# Main_Schematic.net
KiCad netlist of a schematic drawn in Altium Designer
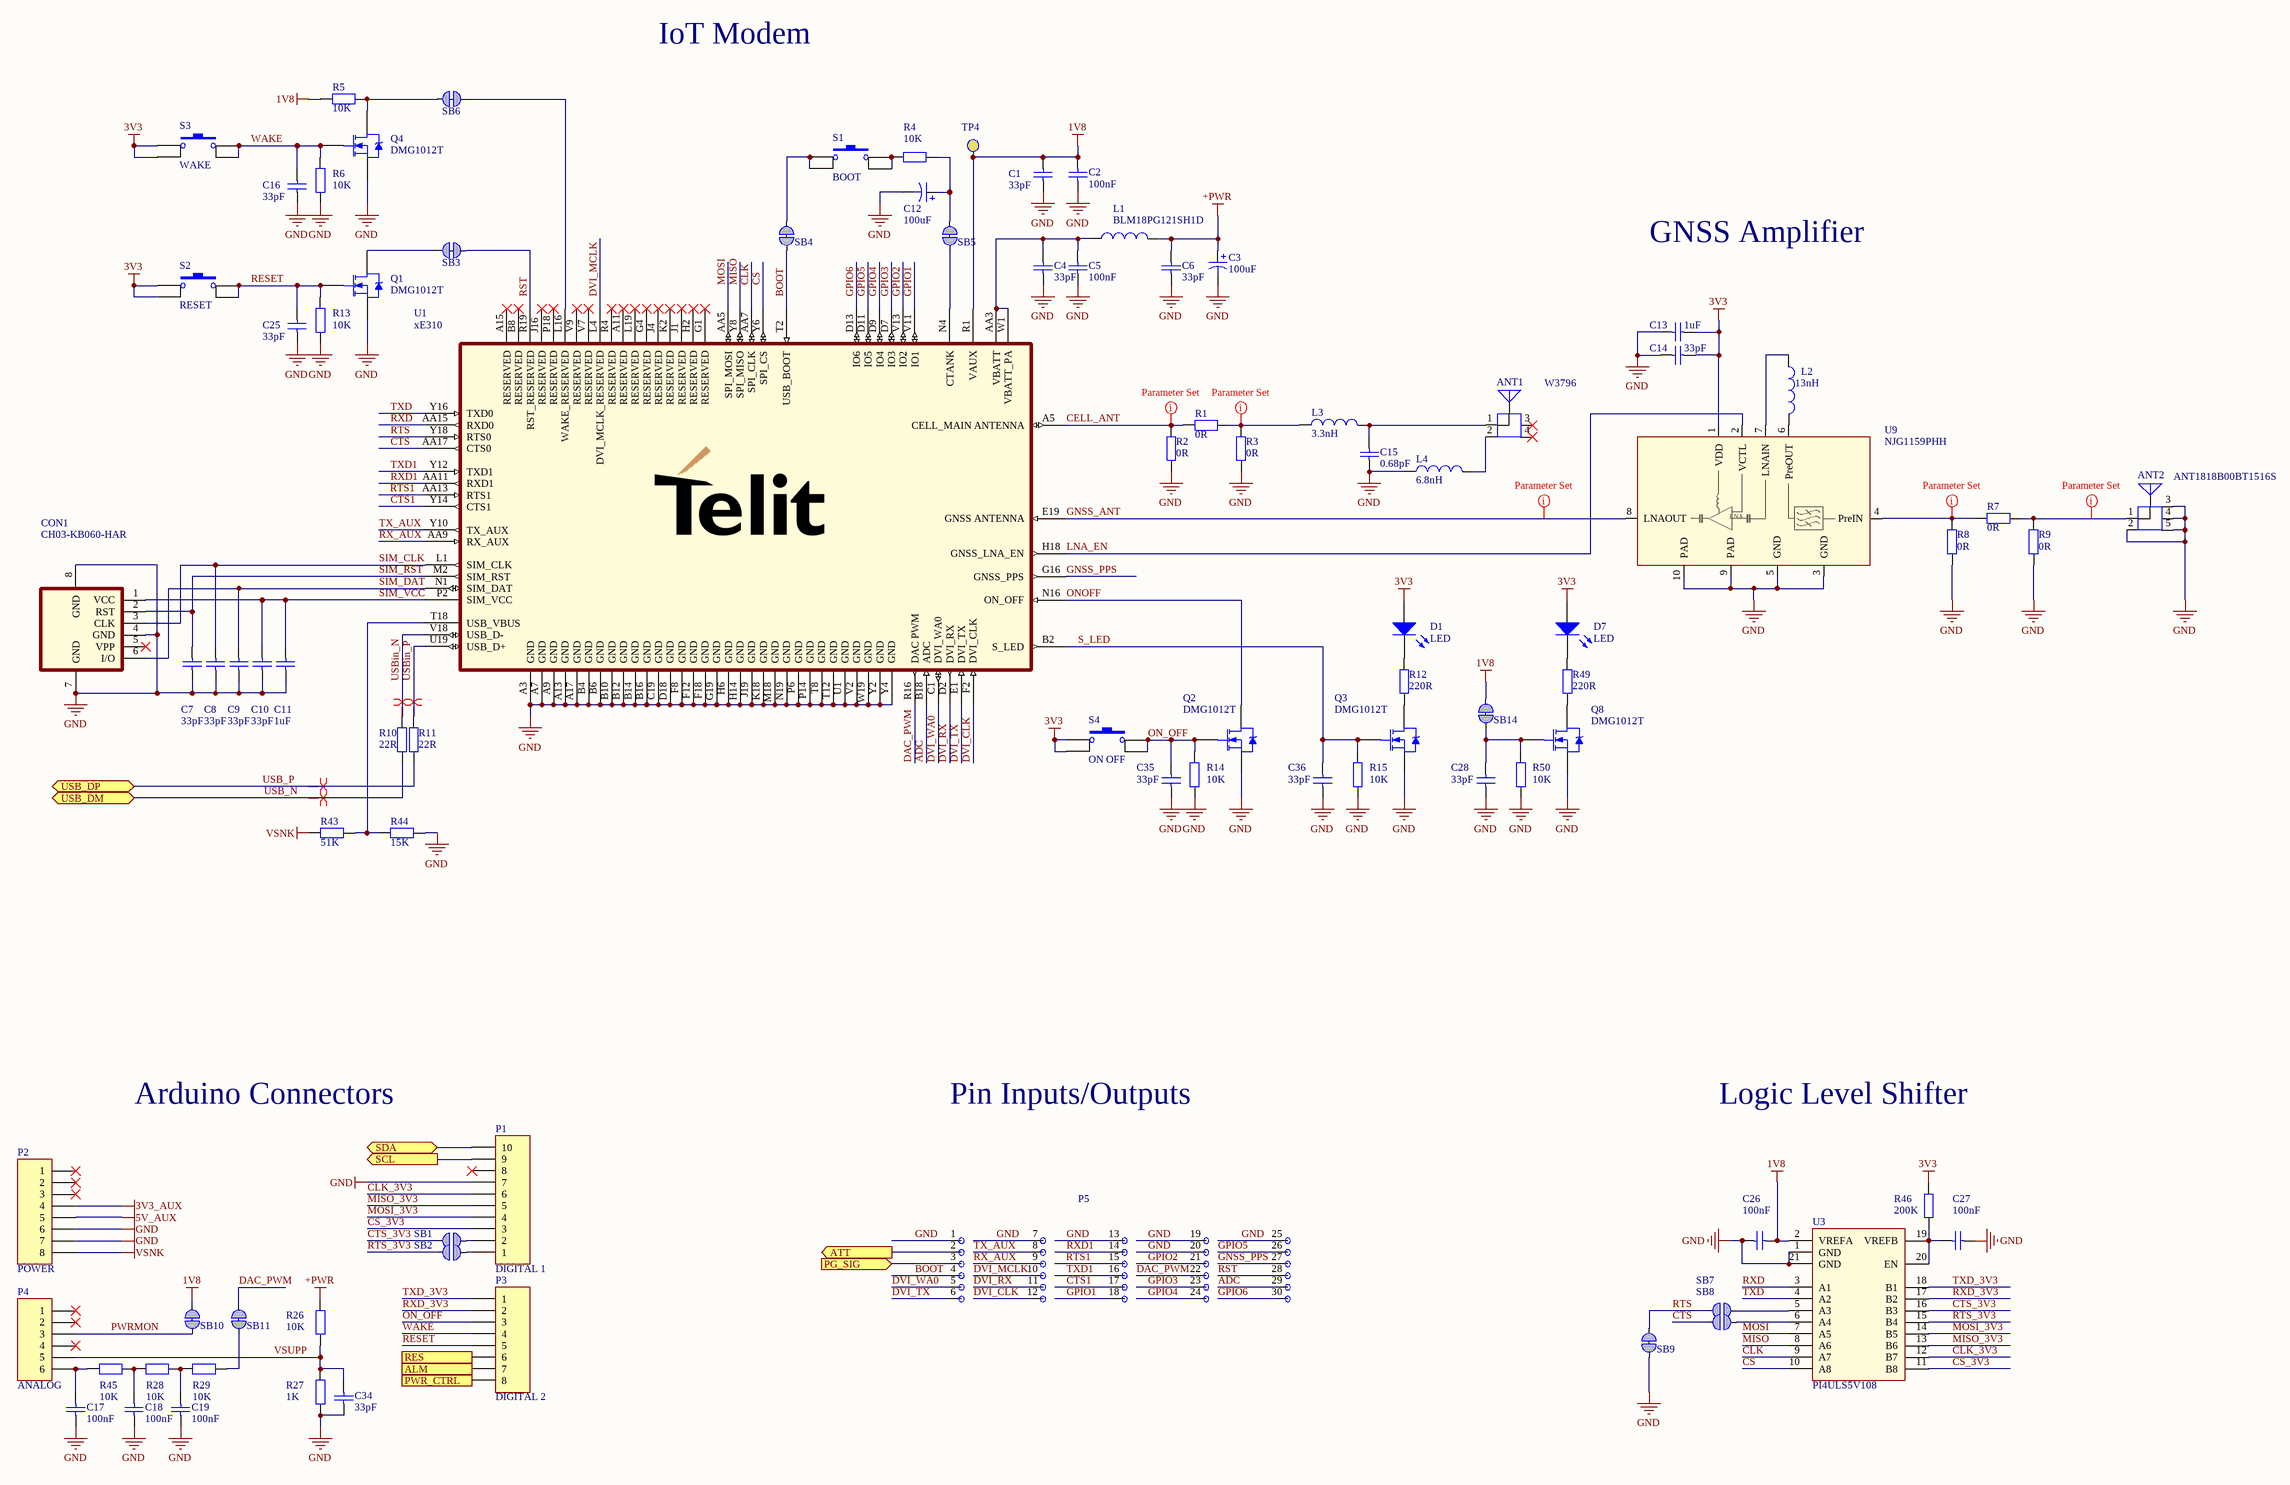
[diagram p0: Main_Schematic.SchDoc]

(export (version "E")
  (design (tool "Eeschema 10.0.6"))
  (components
    (comp (ref "ANT1")
      (value "W3796")
      (footprint "W3796")
      (description "Generic Antenna")
      (fields (field (name "MANUFACTURER") "Pulse"))
      (libsource (lib "RUT_GE310_GNSS") (part "Antenna"))
    )
    (comp (ref "ANT2")
      (value "ANT1818B00BT1516S")
      (footprint "ANT1818B00BT1516S")
      (description "Generic Antenna")
      (fields (field (name "MANUFACTURER") "Yegeo"))
      (libsource (lib "") (part "Antenna_1"))
    )
    (comp (ref "C1")
      (value "33pF")
      (footprint "C0402")
      (description "Capacitor (Semiconductor SIM Model)")
      (fields (field (name "MANUFACTURER") "AVX") (field (name "MANUFACTURER PART NO.") "04025A330JAT2A"))
      (libsource (lib "Miscellaneous Devices") (part "Cap Semi"))
    )
    (comp (ref "C2")
      (value "100nF")
      (footprint "C0402")
      (description "Capacitor (Semiconductor SIM Model)")
      (fields
        (field (name "MANUFACTURER") "YAGEO")
        (field (name "MANUFACTURER PART NO.") "CC0402KRX7R9BB104")
      )
      (libsource (lib "Miscellaneous Devices") (part "Cap Semi"))
    )
    (comp (ref "C3")
      (value "100uF")
      (footprint "Case-B")
      (fields
        (field (name "MANUFACTURER") "AVX")
        (field (name "MANUFACTURER PART NO.") "TPSB107M006R0250")
        (field (name "Comment") "electrolytic capacitor")
      )
      (libsource (lib "Miscellaneous Devices") (part "Cap Pol1"))
    )
    (comp (ref "C4")
      (value "33pF")
      (footprint "C0402")
      (description "Capacitor (Semiconductor SIM Model)")
      (fields (field (name "MANUFACTURER") "AVX") (field (name "MANUFACTURER PART NO.") "04025A330JAT2A"))
      (libsource (lib "Miscellaneous Devices") (part "Cap Semi"))
    )
    (comp (ref "C5")
      (value "100nF")
      (footprint "C0402")
      (description "Capacitor (Semiconductor SIM Model)")
      (fields
        (field (name "MANUFACTURER") "YAGEO")
        (field (name "MANUFACTURER PART NO.") "CC0402KRX7R9BB104")
      )
      (libsource (lib "Miscellaneous Devices") (part "Cap Semi"))
    )
    (comp (ref "C6")
      (value "33pF")
      (footprint "C0402")
      (description "Capacitor (Semiconductor SIM Model)")
      (fields (field (name "MANUFACTURER") "AVX") (field (name "MANUFACTURER PART NO.") "04025A330JAT2A"))
      (libsource (lib "Miscellaneous Devices") (part "Cap Semi"))
    )
    (comp (ref "C7")
      (value "33pF")
      (footprint "C0402")
      (description "Capacitor (Semiconductor SIM Model)")
      (fields (field (name "MANUFACTURER") "AVX") (field (name "MANUFACTURER PART NO.") "04025A330JAT2A"))
      (libsource (lib "Miscellaneous Devices") (part "Cap Semi"))
    )
    (comp (ref "C8")
      (value "33pF")
      (footprint "C0402")
      (description "Capacitor (Semiconductor SIM Model)")
      (fields (field (name "MANUFACTURER") "AVX") (field (name "MANUFACTURER PART NO.") "04025A330JAT2A"))
      (libsource (lib "Miscellaneous Devices") (part "Cap Semi"))
    )
    (comp (ref "C9")
      (value "33pF")
      (footprint "C0402")
      (description "Capacitor (Semiconductor SIM Model)")
      (fields (field (name "MANUFACTURER") "AVX") (field (name "MANUFACTURER PART NO.") "04025A330JAT2A"))
      (libsource (lib "Miscellaneous Devices") (part "Cap Semi"))
    )
    (comp (ref "C10")
      (value "33pF")
      (footprint "C0402")
      (description "Capacitor (Semiconductor SIM Model)")
      (fields (field (name "MANUFACTURER") "AVX") (field (name "MANUFACTURER PART NO.") "04025A330JAT2A"))
      (libsource (lib "Miscellaneous Devices") (part "Cap Semi"))
    )
    (comp (ref "C11")
      (value "1uF")
      (footprint "C0402")
      (description "Capacitor (Semiconductor SIM Model)")
      (fields
        (field (name "MANUFACTURER") "muRata")
        (field (name "MANUFACTURER PART NO.") "GRM155R61E105KA12D")
      )
      (libsource (lib "Miscellaneous Devices") (part "Cap Semi"))
    )
    (comp (ref "C12")
      (value "100uF")
      (footprint "Case-B")
      (fields
        (field (name "MANUFACTURER") "AVX")
        (field (name "MANUFACTURER PART NO.") "TPSB107M006R0250")
        (field (name "Comment") "electrolytic capacitor")
      )
      (libsource (lib "Miscellaneous Devices") (part "Cap Pol1"))
    )
    (comp (ref "C13")
      (value "1uF")
      (footprint "C0402")
      (description "Capacitor (Semiconductor SIM Model)")
      (fields
        (field (name "MANUFACTURER") "muRata")
        (field (name "MANUFACTURER PART NO.") "GRM155R61E105KA12D")
      )
      (libsource (lib "Miscellaneous Devices") (part "Cap Semi"))
    )
    (comp (ref "C14")
      (value "33pF")
      (footprint "C0402")
      (description "Capacitor (Semiconductor SIM Model)")
      (fields (field (name "MANUFACTURER") "AVX") (field (name "MANUFACTURER PART NO.") "04025A330JAT2A"))
      (libsource (lib "Miscellaneous Devices") (part "Cap Semi"))
    )
    (comp (ref "C15")
      (value "0.68pF")
      (footprint "C0402")
      (description "Capacitor (Semiconductor SIM Model)")
      (fields
        (field (name "MANUFACTURER") "YAGEO")
        (field (name "MANUFACTURER PART NO.") "CC0402BRNPO9BNR68")
      )
      (libsource (lib "Miscellaneous Devices") (part "Cap Semi"))
    )
    (comp (ref "C16")
      (value "33pF")
      (footprint "C0402")
      (description "Capacitor (Semiconductor SIM Model)")
      (fields (field (name "MANUFACTURER") "AVX") (field (name "MANUFACTURER PART NO.") "04025A330JAT2A"))
      (libsource (lib "Miscellaneous Devices") (part "Cap Semi"))
    )
    (comp (ref "C17")
      (value "100nF")
      (footprint "C0402")
      (description "Capacitor (Semiconductor SIM Model)")
      (fields
        (field (name "MANUFACTURER") "YAGEO")
        (field (name "MANUFACTURER PART NO.") "CC0402KRX7R9BB104")
      )
      (libsource (lib "Miscellaneous Devices") (part "Cap Semi"))
    )
    (comp (ref "C18")
      (value "100nF")
      (footprint "C0402")
      (description "Capacitor (Semiconductor SIM Model)")
      (fields
        (field (name "MANUFACTURER") "YAGEO")
        (field (name "MANUFACTURER PART NO.") "CC0402KRX7R9BB104")
      )
      (libsource (lib "Miscellaneous Devices") (part "Cap Semi"))
    )
    (comp (ref "C19")
      (value "100nF")
      (footprint "C0402")
      (description "Capacitor (Semiconductor SIM Model)")
      (fields
        (field (name "MANUFACTURER") "YAGEO")
        (field (name "MANUFACTURER PART NO.") "CC0402KRX7R9BB104")
      )
      (libsource (lib "Miscellaneous Devices") (part "Cap Semi"))
    )
    (comp (ref "C25")
      (value "33pF")
      (footprint "C0402")
      (description "Capacitor (Semiconductor SIM Model)")
      (fields (field (name "MANUFACTURER") "AVX") (field (name "MANUFACTURER PART NO.") "04025A330JAT2A"))
      (libsource (lib "Miscellaneous Devices") (part "Cap Semi"))
    )
    (comp (ref "C26")
      (value "100nF")
      (footprint "C0402")
      (description "Capacitor (Semiconductor SIM Model)")
      (fields
        (field (name "MANUFACTURER") "YAGEO")
        (field (name "MANUFACTURER PART NO.") "CC0402KRX7R9BB104")
      )
      (libsource (lib "Miscellaneous Devices") (part "Cap Semi"))
    )
    (comp (ref "C27")
      (value "100nF")
      (footprint "C0402")
      (description "Capacitor (Semiconductor SIM Model)")
      (fields
        (field (name "MANUFACTURER") "YAGEO")
        (field (name "MANUFACTURER PART NO.") "CC0402KRX7R9BB104")
      )
      (libsource (lib "Miscellaneous Devices") (part "Cap Semi"))
    )
    (comp (ref "C28")
      (value "33pF")
      (footprint "C0402")
      (description "Capacitor (Semiconductor SIM Model)")
      (fields (field (name "MANUFACTURER") "AVX") (field (name "MANUFACTURER PART NO.") "04025A330JAT2A"))
      (libsource (lib "Miscellaneous Devices") (part "Cap Semi"))
    )
    (comp (ref "C34")
      (value "33pF")
      (footprint "C0402")
      (description "Capacitor (Semiconductor SIM Model)")
      (fields (field (name "MANUFACTURER") "AVX") (field (name "MANUFACTURER PART NO.") "04025A330JAT2A"))
      (libsource (lib "Miscellaneous Devices") (part "Cap Semi"))
    )
    (comp (ref "C35")
      (value "33pF")
      (footprint "C0402")
      (description "Capacitor (Semiconductor SIM Model)")
      (fields (field (name "MANUFACTURER") "AVX") (field (name "MANUFACTURER PART NO.") "04025A330JAT2A"))
      (libsource (lib "Miscellaneous Devices") (part "Cap Semi"))
    )
    (comp (ref "C36")
      (value "33pF")
      (footprint "C0402")
      (description "Capacitor (Semiconductor SIM Model)")
      (fields (field (name "MANUFACTURER") "AVX") (field (name "MANUFACTURER PART NO.") "04025A330JAT2A"))
      (libsource (lib "Miscellaneous Devices") (part "Cap Semi"))
    )
    (comp (ref "CON1")
      (value "CH03-KB060-HAR")
      (footprint "CH03-KB")
      (description "Nano SIM Card Connector")
      (fields (field (name "MANUFACTURER") "GradConn"))
      (libsource (lib "CH03-KB060-HAR") (part "CH03-KB060-HAR"))
    )
    (comp (ref "D1")
      (value "LED")
      (footprint "PICOLED")
      (description "Typical SMD LED")
      (fields
        (field (name "MANUFACTURER") "OSRAM")
        (field (name "MANUFACTURER PART NO.") "LTQH9G-Q2OO-25-2Z4Y-5-R18")
      )
      (libsource (lib "Miscellaneous Devices") (part "LED2"))
    )
    (comp (ref "D7")
      (value "LED")
      (footprint "PICOLED")
      (description "Typical SMD LED")
      (fields
        (field (name "MANUFACTURER") "OSRAM")
        (field (name "MANUFACTURER PART NO.") "LTQH9G-Q2OO-25-2Z4Y-5-R18")
      )
      (libsource (lib "Miscellaneous Devices") (part "LED2"))
    )
    (comp (ref "L1")
      (value "BLM18PG121SH1D")
      (footprint "L0603")
      (description "Inductor")
      (fields (field (name "MANUFACTURER") "muRata"))
      (libsource (lib "Miscellaneous Devices") (part "Inductor"))
    )
    (comp (ref "L2")
      (value "13nH")
      (footprint "L0402")
      (description "Inductor")
      (fields (field (name "MANUFACTURER") "muRata") (field (name "MANUFACTURER PART NO.") "LQW15AN13NG00D"))
      (libsource (lib "Miscellaneous Devices") (part "Inductor"))
    )
    (comp (ref "L3")
      (value "3.3nH")
      (footprint "L0603")
      (description "Inductor")
      (fields (field (name "MANUFACTURER") "muRata") (field (name "MANUFACTURER PART NO.") "LQG18HN3N3S00D"))
      (libsource (lib "Miscellaneous Devices") (part "Inductor"))
    )
    (comp (ref "L4")
      (value "6.8nH")
      (footprint "L0603")
      (description "Inductor")
      (fields (field (name "MANUFACTURER") "muRata") (field (name "MANUFACTURER PART NO.") "LQW18AN6N8D10D"))
      (libsource (lib "Miscellaneous Devices") (part "Inductor"))
    )
    (comp (ref "P1")
      (value "DIGITAL 1")
      (footprint "HDR1X10")
      (fields
        (field (name "MANUFACTURER") "SparkFun Electronics")
        (field (name "MANUFACTURER PART NO.") "PRT-11417")
      )
      (libsource (lib "Miscellaneous Connectors") (part "Header 10"))
    )
    (comp (ref "P2")
      (value "POWER")
      (footprint "HDR1X8")
      (libsource (lib "Miscellaneous Connectors") (part "Header 8"))
    )
    (comp (ref "P3") (value "DIGITAL 2") (footprint "HDR1X8") (libsource (lib "") (part "Header 8_1")))
    (comp (ref "P4")
      (value "ANALOG")
      (footprint "HDR1X6")
      (libsource (lib "Miscellaneous Connectors") (part "Header 6"))
    )
    (comp (ref "P5")
      (value "THT_Matrix")
      (footprint "THT_Matrix_5x6")
      (description "Pin matrix, 6 rows, 5 columns, 2.54mm pitch")
      (libsource (lib "THT_Matrix") (part "THT_Matrix"))
    )
    (comp (ref "Q1")
      (value "DMG1012T")
      (footprint "SOT-523_custom")
      (description "N-Channel Power MOSFET")
      (fields (field (name "MANUFACTURER") "Diodes Inc.") (field (name "MANUFACTURER PART NO.") "DMG1012T-7"))
      (libsource (lib "Miscellaneous Devices") (part "NMOS-2"))
    )
    (comp (ref "Q2")
      (value "DMG1012T")
      (footprint "SOT-523_custom")
      (description "N-Channel Power MOSFET")
      (fields (field (name "MANUFACTURER") "Diodes Inc.") (field (name "MANUFACTURER PART NO.") "DMG1012T-7"))
      (libsource (lib "Miscellaneous Devices") (part "NMOS-2"))
    )
    (comp (ref "Q3")
      (value "DMG1012T")
      (footprint "SOT-523_custom")
      (description "N-Channel Power MOSFET")
      (fields (field (name "MANUFACTURER") "Diodes Inc.") (field (name "MANUFACTURER PART NO.") "DMG1012T-7"))
      (libsource (lib "Miscellaneous Devices") (part "NMOS-2"))
    )
    (comp (ref "Q4")
      (value "DMG1012T")
      (footprint "SOT-523_custom")
      (description "N-Channel Power MOSFET")
      (fields (field (name "MANUFACTURER") "Diodes Inc.") (field (name "MANUFACTURER PART NO.") "DMG1012T-7"))
      (libsource (lib "Miscellaneous Devices") (part "NMOS-2"))
    )
    (comp (ref "Q8")
      (value "DMG1012T")
      (footprint "SOT-523_custom")
      (description "N-Channel Power MOSFET")
      (fields (field (name "MANUFACTURER") "Diodes Inc.") (field (name "MANUFACTURER PART NO.") "DMG1012T-7"))
      (libsource (lib "Miscellaneous Devices") (part "NMOS-2"))
    )
    (comp (ref "R1")
      (value "0R")
      (footprint "R0402")
      (fields
        (field (name "MANUFACTURER") "YAGEO")
        (field (name "MANUFACTURER PART NO.") "RC0402FR-070RL")
        (field (name "Comment") "Res2")
      )
      (libsource (lib "Miscellaneous Devices") (part "Res2"))
    )
    (comp (ref "R2")
      (value "0R")
      (footprint "R0402")
      (fields
        (field (name "MANUFACTURER") "YAGEO")
        (field (name "MANUFACTURER PART NO.") "RC0402FR-070RL")
        (field (name "Comment") "Res2")
      )
      (libsource (lib "") (part "Res2_2"))
    )
    (comp (ref "R3")
      (value "0R")
      (footprint "R0402")
      (fields
        (field (name "MANUFACTURER") "YAGEO")
        (field (name "MANUFACTURER PART NO.") "RC0402FR-070RL")
        (field (name "Comment") "Res2")
      )
      (libsource (lib "") (part "Res2_2"))
    )
    (comp (ref "R4")
      (value "10K")
      (footprint "R0402")
      (fields
        (field (name "MANUFACTURER") "ASJ")
        (field (name "MANUFACTURER PART NO.") "CR10-103-JK")
        (field (name "Comment") "Res2")
      )
      (libsource (lib "Miscellaneous Devices") (part "Res2"))
    )
    (comp (ref "R5")
      (value "10K")
      (footprint "R0402")
      (fields
        (field (name "MANUFACTURER") "ASJ")
        (field (name "MANUFACTURER PART NO.") "CR10-103-JK")
        (field (name "Comment") "Res2")
      )
      (libsource (lib "Miscellaneous Devices") (part "Res2"))
    )
    (comp (ref "R6")
      (value "10K")
      (footprint "R0402")
      (fields
        (field (name "MANUFACTURER") "ASJ")
        (field (name "MANUFACTURER PART NO.") "CR10-103-JK")
        (field (name "Comment") "Res2")
      )
      (libsource (lib "") (part "Res2_1"))
    )
    (comp (ref "R7")
      (value "0R")
      (footprint "R0402")
      (fields
        (field (name "MANUFACTURER") "YAGEO")
        (field (name "MANUFACTURER PART NO.") "RC0402FR-070RL")
        (field (name "Comment") "Res2")
      )
      (libsource (lib "Miscellaneous Devices") (part "Res2"))
    )
    (comp (ref "R8")
      (value "0R")
      (footprint "R0402")
      (fields
        (field (name "MANUFACTURER") "YAGEO")
        (field (name "MANUFACTURER PART NO.") "RC0402FR-070RL")
        (field (name "Comment") "Res2")
      )
      (libsource (lib "") (part "Res2_2"))
    )
    (comp (ref "R9")
      (value "0R")
      (footprint "R0402")
      (fields
        (field (name "MANUFACTURER") "YAGEO")
        (field (name "MANUFACTURER PART NO.") "RC0402FR-070RL")
        (field (name "Comment") "Res2")
      )
      (libsource (lib "") (part "Res2_2"))
    )
    (comp (ref "R10")
      (value "22R")
      (footprint "R0402")
      (fields
        (field (name "MANUFACTURER") "ASJ")
        (field (name "MANUFACTURER PART NO.") "CR10-220-JK")
        (field (name "Comment") "Res2")
      )
      (libsource (lib "") (part "Res2_1"))
    )
    (comp (ref "R11")
      (value "22R")
      (footprint "R0402")
      (fields
        (field (name "MANUFACTURER") "ASJ")
        (field (name "MANUFACTURER PART NO.") "CR10-220-JK")
        (field (name "Comment") "Res2")
      )
      (libsource (lib "") (part "Res2_1"))
    )
    (comp (ref "R12")
      (value "220R")
      (footprint "R0402")
      (fields
        (field (name "MANUFACTURER") "ASJ")
        (field (name "MANUFACTURER PART NO.") "CR10-221-JK")
        (field (name "Comment") "Res2")
      )
      (libsource (lib "") (part "Res2_2"))
    )
    (comp (ref "R13")
      (value "10K")
      (footprint "R0402")
      (fields
        (field (name "MANUFACTURER") "ASJ")
        (field (name "MANUFACTURER PART NO.") "CR10-103-JK")
        (field (name "Comment") "Res2")
      )
      (libsource (lib "") (part "Res2_1"))
    )
    (comp (ref "R14")
      (value "10K")
      (footprint "R0402")
      (fields
        (field (name "MANUFACTURER") "ASJ")
        (field (name "MANUFACTURER PART NO.") "CR10-103-JK")
        (field (name "Comment") "Res2")
      )
      (libsource (lib "") (part "Res2_1"))
    )
    (comp (ref "R15")
      (value "10K")
      (footprint "R0402")
      (fields
        (field (name "MANUFACTURER") "ASJ")
        (field (name "MANUFACTURER PART NO.") "CR10-103-JK")
        (field (name "Comment") "Res2")
      )
      (libsource (lib "") (part "Res2_1"))
    )
    (comp (ref "R26")
      (value "10K")
      (footprint "R0402")
      (fields
        (field (name "MANUFACTURER") "ASJ")
        (field (name "MANUFACTURER PART NO.") "CR10-103-JK")
        (field (name "Comment") "Res2")
      )
      (libsource (lib "") (part "Res2_1"))
    )
    (comp (ref "R27")
      (value "1K")
      (footprint "R0402")
      (fields
        (field (name "MANUFACTURER") "ASJ")
        (field (name "MANUFACTURER PART NO.") "CR10-102-JK")
        (field (name "Comment") "Res2")
      )
      (libsource (lib "") (part "Res2_1"))
    )
    (comp (ref "R28")
      (value "10K")
      (footprint "R0402")
      (fields
        (field (name "MANUFACTURER") "ASJ")
        (field (name "MANUFACTURER PART NO.") "CR10-103-JK")
        (field (name "Comment") "Res2")
      )
      (libsource (lib "Miscellaneous Devices") (part "Res2"))
    )
    (comp (ref "R29")
      (value "10K")
      (footprint "R0402")
      (fields
        (field (name "MANUFACTURER") "ASJ")
        (field (name "MANUFACTURER PART NO.") "CR10-103-JK")
        (field (name "Comment") "Res2")
      )
      (libsource (lib "Miscellaneous Devices") (part "Res2"))
    )
    (comp (ref "R43")
      (value "51K")
      (footprint "R0402")
      (fields
        (field (name "MANUFACTURER") "YAGEO")
        (field (name "MANUFACTURER PART NO.") "RC0402JR-0751KL")
        (field (name "Comment") "Res2")
      )
      (libsource (lib "Miscellaneous Devices") (part "Res2"))
    )
    (comp (ref "R44")
      (value "15K")
      (footprint "R0402")
      (fields
        (field (name "MANUFACTURER") "ASJ")
        (field (name "MANUFACTURER PART NO.") "CR10-153-JK")
        (field (name "Comment") "Res2")
      )
      (libsource (lib "Miscellaneous Devices") (part "Res2"))
    )
    (comp (ref "R45")
      (value "10K")
      (footprint "R0402")
      (fields
        (field (name "MANUFACTURER") "ASJ")
        (field (name "MANUFACTURER PART NO.") "CR10-103-JK")
        (field (name "Comment") "Res2")
      )
      (libsource (lib "Miscellaneous Devices") (part "Res2"))
    )
    (comp (ref "R46")
      (value "200K")
      (footprint "R0402")
      (fields
        (field (name "MANUFACTURER") "ASJ")
        (field (name "MANUFACTURER PART NO.") "CR10-204-JK")
        (field (name "Comment") "Res2")
      )
      (libsource (lib "") (part "Res2_1"))
    )
    (comp (ref "R49")
      (value "220R")
      (footprint "R0402")
      (fields
        (field (name "MANUFACTURER") "ASJ")
        (field (name "MANUFACTURER PART NO.") "CR10-221-JK")
        (field (name "Comment") "Res2")
      )
      (libsource (lib "") (part "Res2_2"))
    )
    (comp (ref "R50")
      (value "10K")
      (footprint "R0402")
      (fields
        (field (name "MANUFACTURER") "ASJ")
        (field (name "MANUFACTURER PART NO.") "CR10-103-JK")
        (field (name "Comment") "Res2")
      )
      (libsource (lib "") (part "Res2_1"))
    )
    (comp (ref "S1")
      (value "BOOT")
      (footprint "EVPAA002K")
      (description "Switch")
      (fields (field (name "MANUFACTURER") "Panasonic") (field (name "MANUFACTURER PART NO.") "EVPAA002K"))
      (libsource (lib "RUT_xE310_GNSS") (part "EVPAA002K"))
    )
    (comp (ref "S2")
      (value "RESET")
      (footprint "EVPAA002K")
      (description "Switch")
      (fields (field (name "MANUFACTURER") "Panasonic") (field (name "MANUFACTURER PART NO.") "EVPAA002K"))
      (libsource (lib "RUT_xE310_GNSS") (part "EVPAA002K"))
    )
    (comp (ref "S3")
      (value "WAKE")
      (footprint "EVPAA002K")
      (description "Switch")
      (fields (field (name "MANUFACTURER") "Panasonic") (field (name "MANUFACTURER PART NO.") "EVPAA002K"))
      (libsource (lib "RUT_xE310_GNSS") (part "EVPAA002K"))
    )
    (comp (ref "S4")
      (value "ON OFF")
      (footprint "EVQPUA")
      (description "Switch")
      (fields (field (name "MANUFACTURER") "Panasonic") (field (name "MANUFACTURER PART NO.") "EVQPUJ02K"))
      (libsource (lib "RUT_GE310_GNSS") (part "SW-PB"))
    )
    (comp (ref "SB1")
      (value "Solderbridge")
      (footprint "Solderbridge")
      (libsource (lib "altium-import") (part "root_2_SOLDERBRIDGE_"))
    )
    (comp (ref "SB2")
      (value "Solderbridge")
      (footprint "Solderbridge")
      (libsource (lib "altium-import") (part "root_2_SOLDERBRIDGE_"))
    )
    (comp (ref "SB3")
      (value "Solderbridge")
      (footprint "Solderbridge_Shorted")
      (libsource (lib "altium-import") (part "root_0_SOLDERBRIDGE_SHORTED_"))
    )
    (comp (ref "SB4")
      (value "Solderbridge")
      (footprint "Solderbridge_Shorted")
      (libsource (lib "altium-import") (part "root_1_SOLDERBRIDGE_SHORTED_"))
    )
    (comp (ref "SB5")
      (value "Solderbridge")
      (footprint "Solderbridge_Shorted")
      (libsource (lib "altium-import") (part "root_1_SOLDERBRIDGE_SHORTED_"))
    )
    (comp (ref "SB6")
      (value "Solderbridge")
      (footprint "Solderbridge_Shorted")
      (libsource (lib "altium-import") (part "root_0_SOLDERBRIDGE_SHORTED_"))
    )
    (comp (ref "SB7")
      (value "Solderbridge")
      (footprint "Solderbridge")
      (libsource (lib "altium-import") (part "root_2_SOLDERBRIDGE_"))
    )
    (comp (ref "SB8")
      (value "Solderbridge")
      (footprint "Solderbridge")
      (libsource (lib "altium-import") (part "root_2_SOLDERBRIDGE_"))
    )
    (comp (ref "SB9")
      (value "Solderbridge")
      (footprint "Solderbridge_Shorted")
      (libsource (lib "altium-import") (part "root_1_SOLDERBRIDGE_SHORTED_"))
    )
    (comp (ref "SB10")
      (value "Solderbridge")
      (footprint "Solderbridge_Shorted")
      (libsource (lib "altium-import") (part "root_1_SOLDERBRIDGE_SHORTED_"))
    )
    (comp (ref "SB11")
      (value "Solderbridge")
      (footprint "Solderbridge_Shorted")
      (libsource (lib "altium-import") (part "root_1_SOLDERBRIDGE_SHORTED_"))
    )
    (comp (ref "SB14")
      (value "Solderbridge")
      (footprint "Solderbridge_Shorted")
      (libsource (lib "altium-import") (part "root_1_SOLDERBRIDGE_SHORTED_"))
    )
    (comp (ref "TP4")
      (value "Test_Point")
      (footprint "TEST_POINT")
      (description "Test Point")
      (libsource (lib "Test Point") (part "Test_Point"))
    )
    (comp (ref "U1")
      (value "xE310")
      (footprint "LGA_GE310")
      (description "xE310-GNSS IoT Modem")
      (fields (field (name "MANUFACTURER") "Telit") (field (name "MANUFACTURER PART NO.") "ME310G1-WW"))
      (libsource (lib "ME310-GNSS") (part "xE310-GNSS"))
    )
    (comp (ref "U3")
      (value "PI4ULS5V108")
      (footprint "VQFN-20")
      (description "8-Bit Bi-directional Level Shifter for Open-Drain and Push-Pull Application")
      (fields (field (name "MANUFACTURER") "Diodes Inc."))
      (libsource (lib "PI4ULS5V108") (part "PI4ULS5V108"))
    )
    (comp (ref "U9")
      (value "NJG1159PHH")
      (footprint "HFFP10-HH")
      (description "GNSS Front-End Module")
      (fields
        (field (name "MANUFACTURER") "New Japan Radio")
        (field (name "MANUFACTURER PART NO.") "NJG1159PHH-TE1")
      )
      (libsource (lib "NJG1159PHH") (part "NJG1159PHH"))
    )
  )
  (nets
    (net (code "1") (name "+PWR") (class "Default")
      (node (ref "C3") (pin "1") (pinfunction "1_1") (pintype "passive"))
      (node (ref "C6") (pin "2") (pinfunction "2_2") (pintype "passive"))
      (node (ref "L1") (pin "2") (pinfunction "2_2") (pintype "passive"))
      (node (ref "R26") (pin "2") (pinfunction "2_2") (pintype "passive"))
    )
    (net (code "3") (name "/ADC") (class "Default")
      (node (ref "P5") (pin "29") (pinfunction "29_29") (pintype "passive"))
      (node (ref "U1") (pin "B18") (pinfunction "ADC_B18") (pintype "input"))
    )
    (net (code "4") (name "/ALM") (class "Default")
      (node (ref "P3") (pin "7") (pinfunction "7_7") (pintype "passive"))
    )
    (net (code "5") (name "/ATT") (class "Default")
      (node (ref "P5") (pin "2") (pinfunction "2_2") (pintype "passive"))
    )
    (net (code "6") (name "/BOOT") (class "Default")
      (node (ref "P5") (pin "4") (pinfunction "4_4") (pintype "passive"))
      (node (ref "SB4") (pin "2") (pinfunction "1_2") (pintype "passive"))
      (node (ref "U1") (pin "T2") (pinfunction "USB_BOOT_T2") (pintype "input"))
    )
    (net (code "7") (name "/CELL_ANT") (class "Default")
      (node (ref "R1") (pin "2") (pinfunction "2_2") (pintype "passive"))
      (node (ref "R2") (pin "1") (pinfunction "1_1") (pintype "passive"))
      (node (ref "U1") (pin "A5") (pinfunction "CELL_MAIN_ANTENNA_A5") (pintype "bidirectional"))
    )
    (net (code "8") (name "/CLK") (class "Default")
      (node (ref "U1") (pin "AA7") (pinfunction "SPI_CLK_AA7") (pintype "bidirectional"))
      (node (ref "U3") (pin "9") (pinfunction "A7_9") (pintype "passive"))
    )
    (net (code "9") (name "/CLK_3V3") (class "Default")
      (node (ref "P1") (pin "6") (pinfunction "6_6") (pintype "passive"))
      (node (ref "U3") (pin "12") (pinfunction "B7_12") (pintype "passive"))
    )
    (net (code "10") (name "/CS") (class "Default")
      (node (ref "U1") (pin "Y6") (pinfunction "SPI_CS_Y6") (pintype "bidirectional"))
      (node (ref "U3") (pin "10") (pinfunction "A8_10") (pintype "passive"))
    )
    (net (code "11") (name "/CS_3V3") (class "Default")
      (node (ref "P1") (pin "3") (pinfunction "3_3") (pintype "passive"))
      (node (ref "U3") (pin "11") (pinfunction "B8_11") (pintype "passive"))
    )
    (net (code "12") (name "/CTS") (class "Default")
      (node (ref "SB8") (pin "1") (pinfunction "0_1") (pintype "passive"))
      (node (ref "U1") (pin "AA17") (pinfunction "CTS0_AA17") (pintype "output"))
    )
    (net (code "13") (name "/CTS1") (class "Default")
      (node (ref "P5") (pin "17") (pinfunction "17_17") (pintype "passive"))
      (node (ref "U1") (pin "Y14") (pinfunction "CTS1_Y14") (pintype "output"))
    )
    (net (code "14") (name "/CTS_3V3") (class "Default")
      (node (ref "SB1") (pin "1") (pinfunction "0_1") (pintype "passive"))
      (node (ref "U3") (pin "16") (pinfunction "B3_16") (pintype "passive"))
    )
    (net (code "15") (name "/DAC_PWM") (class "Default")
      (node (ref "P5") (pin "22") (pinfunction "22_22") (pintype "passive"))
      (node (ref "SB11") (pin "1") (pinfunction "0_1") (pintype "passive"))
      (node (ref "U1") (pin "R16") (pinfunction "DAC_PWM_R16") (pintype "output"))
    )
    (net (code "16") (name "/DVI_CLK") (class "Default")
      (node (ref "P5") (pin "12") (pinfunction "12_12") (pintype "passive"))
      (node (ref "U1") (pin "F2") (pinfunction "DVI_CLK_F2") (pintype "input"))
    )
    (net (code "17") (name "/DVI_MCLK") (class "Default")
      (node (ref "P5") (pin "10") (pinfunction "10_10") (pintype "passive"))
      (node (ref "U1") (pin "L4") (pinfunction "DVI_MCLK_RESERVED_L4") (pintype "passive"))
    )
    (net (code "18") (name "/DVI_RX") (class "Default")
      (node (ref "P5") (pin "11") (pinfunction "11_11") (pintype "passive"))
      (node (ref "U1") (pin "D2") (pinfunction "DVI_RX_D2") (pintype "output"))
    )
    (net (code "19") (name "/DVI_TX") (class "Default")
      (node (ref "P5") (pin "6") (pinfunction "6_6") (pintype "passive"))
      (node (ref "U1") (pin "E1") (pinfunction "DVI_TX_E1") (pintype "input"))
    )
    (net (code "20") (name "/DVI_WA0") (class "Default")
      (node (ref "P5") (pin "5") (pinfunction "5_5") (pintype "passive"))
      (node (ref "U1") (pin "C1") (pinfunction "DVI_WA0_C1") (pintype "bidirectional"))
    )
    (net (code "21") (name "/GNSS_ANT") (class "Default")
      (node (ref "U1") (pin "E19") (pinfunction "GNSS_ANTENNA_E19") (pintype "input"))
      (node (ref "U9") (pin "8") (pinfunction "LNAOUT_8") (pintype "passive"))
    )
    (net (code "22") (name "/GNSS_PPS") (class "Default")
      (node (ref "P5") (pin "27") (pinfunction "27_27") (pintype "passive"))
      (node (ref "U1") (pin "G16") (pinfunction "GNSS_PPS_G16") (pintype "output"))
    )
    (net (code "23") (name "/GPIO1") (class "Default")
      (node (ref "P5") (pin "18") (pinfunction "18_18") (pintype "passive"))
      (node (ref "U1") (pin "V11") (pinfunction "IO1_V11") (pintype "bidirectional"))
    )
    (net (code "24") (name "/GPIO2") (class "Default")
      (node (ref "P5") (pin "21") (pinfunction "21_21") (pintype "passive"))
      (node (ref "U1") (pin "V13") (pinfunction "IO2_V13") (pintype "bidirectional"))
    )
    (net (code "25") (name "/GPIO3") (class "Default")
      (node (ref "P5") (pin "23") (pinfunction "23_23") (pintype "passive"))
      (node (ref "U1") (pin "D7") (pinfunction "IO3_D7") (pintype "bidirectional"))
    )
    (net (code "26") (name "/GPIO4") (class "Default")
      (node (ref "P5") (pin "24") (pinfunction "24_24") (pintype "passive"))
      (node (ref "U1") (pin "D9") (pinfunction "IO4_D9") (pintype "bidirectional"))
    )
    (net (code "27") (name "/GPIO5") (class "Default")
      (node (ref "P5") (pin "26") (pinfunction "26_26") (pintype "passive"))
      (node (ref "U1") (pin "D11") (pinfunction "IO5_D11") (pintype "bidirectional"))
    )
    (net (code "28") (name "/GPIO6") (class "Default")
      (node (ref "P5") (pin "30") (pinfunction "30_30") (pintype "passive"))
      (node (ref "U1") (pin "D13") (pinfunction "IO6_D13") (pintype "bidirectional"))
    )
    (net (code "29") (name "/LNA_EN") (class "Default")
      (node (ref "U1") (pin "H18") (pinfunction "GNSS_LNA_EN_H18") (pintype "output"))
      (node (ref "U9") (pin "2") (pinfunction "VCTL_2") (pintype "passive"))
    )
    (net (code "30") (name "/MISO") (class "Default")
      (node (ref "U1") (pin "Y8") (pinfunction "SPI_MISO_Y8") (pintype "bidirectional"))
      (node (ref "U3") (pin "8") (pinfunction "A6_8") (pintype "passive"))
    )
    (net (code "31") (name "/MISO_3V3") (class "Default")
      (node (ref "P1") (pin "5") (pinfunction "5_5") (pintype "passive"))
      (node (ref "U3") (pin "13") (pinfunction "B6_13") (pintype "passive"))
    )
    (net (code "32") (name "/MOSI") (class "Default")
      (node (ref "U1") (pin "AA5") (pinfunction "SPI_MOSI_AA5") (pintype "bidirectional"))
      (node (ref "U3") (pin "7") (pinfunction "A5_7") (pintype "passive"))
    )
    (net (code "33") (name "/MOSI_3V3") (class "Default")
      (node (ref "P1") (pin "4") (pinfunction "4_4") (pintype "passive"))
      (node (ref "U3") (pin "14") (pinfunction "B5_14") (pintype "passive"))
    )
    (net (code "34") (name "/ONOFF") (class "Default")
      (node (ref "Q2") (pin "2") (pinfunction "D_2") (pintype "passive"))
      (node (ref "U1") (pin "N16") (pinfunction "ON_OFF_N16") (pintype "input"))
    )
    (net (code "35") (name "/ON_OFF") (class "Default")
      (node (ref "C35") (pin "1") (pinfunction "1_1") (pintype "passive"))
      (node (ref "P3") (pin "3") (pinfunction "3_3") (pintype "passive"))
      (node (ref "Q2") (pin "1") (pinfunction "G_1") (pintype "passive"))
      (node (ref "R14") (pin "2") (pinfunction "2_2") (pintype "passive"))
      (node (ref "S4") (pin "2") (pinfunction "2_2") (pintype "passive"))
      (node (ref "S4") (pin "4") (pinfunction "4_4") (pintype "passive"))
    )
    (net (code "36") (name "/PG_SIG") (class "Default")
      (node (ref "P5") (pin "3") (pinfunction "3_3") (pintype "passive"))
    )
    (net (code "37") (name "/PWRMON") (class "Default")
      (node (ref "P4") (pin "3") (pinfunction "3_3") (pintype "passive"))
      (node (ref "SB10") (pin "2") (pinfunction "1_2") (pintype "passive"))
    )
    (net (code "38") (name "/PWR_CTRL") (class "Default")
      (node (ref "P3") (pin "8") (pinfunction "8_8") (pintype "passive"))
    )
    (net (code "39") (name "/RES") (class "Default")
      (node (ref "P3") (pin "6") (pinfunction "6_6") (pintype "passive"))
    )
    (net (code "40") (name "/RESET") (class "Default")
      (node (ref "C25") (pin "1") (pinfunction "1_1") (pintype "passive"))
      (node (ref "P3") (pin "5") (pinfunction "5_5") (pintype "passive"))
      (node (ref "Q1") (pin "1") (pinfunction "G_1") (pintype "passive"))
      (node (ref "R13") (pin "2") (pinfunction "2_2") (pintype "passive"))
      (node (ref "S2") (pin "2") (pinfunction "2_2") (pintype "passive"))
      (node (ref "S2") (pin "3") (pinfunction "3_3") (pintype "passive"))
    )
    (net (code "41") (name "/RST") (class "Default")
      (node (ref "P5") (pin "28") (pinfunction "28_28") (pintype "passive"))
      (node (ref "SB3") (pin "1") (pinfunction "0_1") (pintype "passive"))
      (node (ref "U1") (pin "R19") (pinfunction "RST_RESERVED_R19") (pintype "passive"))
    )
    (net (code "42") (name "/RTS") (class "Default")
      (node (ref "SB7") (pin "1") (pinfunction "0_1") (pintype "passive"))
      (node (ref "SB9") (pin "1") (pinfunction "0_1") (pintype "passive"))
      (node (ref "U1") (pin "Y18") (pinfunction "RTS0_Y18") (pintype "input"))
    )
    (net (code "43") (name "/RTS1") (class "Default")
      (node (ref "P5") (pin "15") (pinfunction "15_15") (pintype "passive"))
      (node (ref "U1") (pin "AA13") (pinfunction "RTS1_AA13") (pintype "input"))
    )
    (net (code "44") (name "/RTS_3V3") (class "Default")
      (node (ref "SB2") (pin "1") (pinfunction "0_1") (pintype "passive"))
      (node (ref "U3") (pin "15") (pinfunction "B4_15") (pintype "passive"))
    )
    (net (code "45") (name "/RXD") (class "Default")
      (node (ref "U1") (pin "AA15") (pinfunction "RXD0_AA15") (pintype "output"))
      (node (ref "U3") (pin "3") (pinfunction "A1_3") (pintype "passive"))
    )
    (net (code "46") (name "/RXD1") (class "Default")
      (node (ref "P5") (pin "14") (pinfunction "14_14") (pintype "passive"))
      (node (ref "U1") (pin "AA11") (pinfunction "RXD1_AA11") (pintype "output"))
    )
    (net (code "47") (name "/RXD_3V3") (class "Default")
      (node (ref "P3") (pin "2") (pinfunction "2_2") (pintype "passive"))
      (node (ref "U3") (pin "17") (pinfunction "B2_17") (pintype "passive"))
    )
    (net (code "48") (name "/RX_AUX") (class "Default")
      (node (ref "P5") (pin "9") (pinfunction "9_9") (pintype "passive"))
      (node (ref "U1") (pin "AA9") (pinfunction "RX_AUX_AA9") (pintype "input"))
    )
    (net (code "49") (name "/SCL") (class "Default")
      (node (ref "P1") (pin "9") (pinfunction "9_9") (pintype "passive"))
    )
    (net (code "50") (name "/SDA") (class "Default")
      (node (ref "P1") (pin "10") (pinfunction "10_10") (pintype "passive"))
    )
    (net (code "51") (name "/SIM_CLK") (class "Default")
      (node (ref "C8") (pin "1") (pinfunction "1_1") (pintype "passive"))
      (node (ref "CON1") (pin "3") (pinfunction "CLK_3") (pintype "passive"))
      (node (ref "U1") (pin "L1") (pinfunction "SIM_CLK_L1") (pintype "output"))
    )
    (net (code "52") (name "/SIM_DAT") (class "Default")
      (node (ref "C9") (pin "1") (pinfunction "1_1") (pintype "passive"))
      (node (ref "CON1") (pin "6") (pinfunction "I/O_6") (pintype "passive"))
      (node (ref "U1") (pin "N1") (pinfunction "SIM_DAT_N1") (pintype "bidirectional"))
    )
    (net (code "53") (name "/SIM_RST") (class "Default")
      (node (ref "C7") (pin "1") (pinfunction "1_1") (pintype "passive"))
      (node (ref "CON1") (pin "2") (pinfunction "RST_2") (pintype "passive"))
      (node (ref "U1") (pin "M2") (pinfunction "SIM_RST_M2") (pintype "output"))
    )
    (net (code "54") (name "/SIM_VCC") (class "Default")
      (node (ref "C10") (pin "1") (pinfunction "1_1") (pintype "passive"))
      (node (ref "C11") (pin "2") (pinfunction "2_2") (pintype "passive"))
      (node (ref "CON1") (pin "1") (pinfunction "VCC_1") (pintype "passive"))
      (node (ref "U1") (pin "P2") (pinfunction "SIM_VCC_P2") (pintype "power_in"))
    )
    (net (code "55") (name "/S_LED") (class "Default")
      (node (ref "C36") (pin "1") (pinfunction "1_1") (pintype "passive"))
      (node (ref "Q3") (pin "1") (pinfunction "G_1") (pintype "passive"))
      (node (ref "R15") (pin "2") (pinfunction "2_2") (pintype "passive"))
      (node (ref "U1") (pin "B2") (pinfunction "S_LED_B2") (pintype "output"))
    )
    (net (code "56") (name "/TXD") (class "Default")
      (node (ref "U1") (pin "Y16") (pinfunction "TXD0_Y16") (pintype "input"))
      (node (ref "U3") (pin "4") (pinfunction "A2_4") (pintype "passive"))
    )
    (net (code "57") (name "/TXD1") (class "Default")
      (node (ref "P5") (pin "16") (pinfunction "16_16") (pintype "passive"))
      (node (ref "U1") (pin "Y12") (pinfunction "TXD1_Y12") (pintype "input"))
    )
    (net (code "58") (name "/TXD_3V3") (class "Default")
      (node (ref "P3") (pin "1") (pinfunction "1_1") (pintype "passive"))
      (node (ref "U3") (pin "18") (pinfunction "B1_18") (pintype "passive"))
    )
    (net (code "59") (name "/TX_AUX") (class "Default")
      (node (ref "P5") (pin "8") (pinfunction "8_8") (pintype "passive"))
      (node (ref "U1") (pin "Y10") (pinfunction "TX_AUX_Y10") (pintype "output"))
    )
    (net (code "60") (name "/USB_N") (class "Default")
      (node (ref "R10") (pin "1") (pinfunction "1_1") (pintype "passive"))
    )
    (net (code "61") (name "/USB_P") (class "Default")
      (node (ref "R11") (pin "1") (pinfunction "1_1") (pintype "passive"))
    )
    (net (code "62") (name "/USBin_N") (class "Default")
      (node (ref "R10") (pin "2") (pinfunction "2_2") (pintype "passive"))
      (node (ref "U1") (pin "V18") (pinfunction "USB_D-_V18") (pintype "bidirectional"))
    )
    (net (code "63") (name "/USBin_P") (class "Default")
      (node (ref "R11") (pin "2") (pinfunction "2_2") (pintype "passive"))
      (node (ref "U1") (pin "U19") (pinfunction "USB_D+_U19") (pintype "bidirectional"))
    )
    (net (code "64") (name "/VSUPP") (class "Default")
      (node (ref "C34") (pin "2") (pinfunction "2_2") (pintype "passive"))
      (node (ref "P4") (pin "5") (pinfunction "5_5") (pintype "passive"))
      (node (ref "R26") (pin "1") (pinfunction "1_1") (pintype "passive"))
      (node (ref "R27") (pin "2") (pinfunction "2_2") (pintype "passive"))
    )
    (net (code "65") (name "/WAKE") (class "Default")
      (node (ref "C16") (pin "1") (pinfunction "1_1") (pintype "passive"))
      (node (ref "P3") (pin "4") (pinfunction "4_4") (pintype "passive"))
      (node (ref "Q4") (pin "1") (pinfunction "G_1") (pintype "passive"))
      (node (ref "R6") (pin "2") (pinfunction "2_2") (pintype "passive"))
      (node (ref "S3") (pin "2") (pinfunction "2_2") (pintype "passive"))
      (node (ref "S3") (pin "3") (pinfunction "3_3") (pintype "passive"))
    )
    (net (code "66") (name "1V8") (class "Default")
      (node (ref "C1") (pin "1") (pinfunction "1_1") (pintype "passive"))
      (node (ref "C2") (pin "2") (pinfunction "2_2") (pintype "passive"))
      (node (ref "C26") (pin "2") (pinfunction "2_2") (pintype "passive"))
      (node (ref "R5") (pin "2") (pinfunction "2_2") (pintype "passive"))
      (node (ref "SB10") (pin "1") (pinfunction "0_1") (pintype "passive"))
      (node (ref "SB14") (pin "1") (pinfunction "0_1") (pintype "passive"))
      (node (ref "TP4") (pin "0") (pinfunction "0_0") (pintype "passive"))
      (node (ref "U1") (pin "R1") (pinfunction "VAUX_R1") (pintype "power_in"))
      (node (ref "U3") (pin "2") (pinfunction "VREFA_2") (pintype "passive"))
    )
    (net (code "67") (name "3V3") (class "Default")
      (node (ref "C13") (pin "1") (pinfunction "1_1") (pintype "passive"))
      (node (ref "C14") (pin "1") (pinfunction "1_1") (pintype "passive"))
      (node (ref "D1") (pin "1") (pinfunction "A_1") (pintype "passive"))
      (node (ref "D7") (pin "1") (pinfunction "A_1") (pintype "passive"))
      (node (ref "R46") (pin "2") (pinfunction "2_2") (pintype "passive"))
      (node (ref "S2") (pin "1") (pinfunction "1_1") (pintype "passive"))
      (node (ref "S2") (pin "4") (pinfunction "4_4") (pintype "passive"))
      (node (ref "S3") (pin "1") (pinfunction "1_1") (pintype "passive"))
      (node (ref "S3") (pin "4") (pinfunction "4_4") (pintype "passive"))
      (node (ref "S4") (pin "1") (pinfunction "1_1") (pintype "passive"))
      (node (ref "S4") (pin "3") (pinfunction "3_3") (pintype "passive"))
      (node (ref "U9") (pin "1") (pinfunction "VDD_1") (pintype "passive"))
    )
    (net (code "68") (name "3V3_AUX") (class "Default")
      (node (ref "P2") (pin "4") (pinfunction "4_4") (pintype "passive"))
    )
    (net (code "69") (name "5V_AUX") (class "Default")
      (node (ref "P2") (pin "5") (pinfunction "5_5") (pintype "passive"))
    )
    (net (code "70") (name "GND") (class "Default")
      (node (ref "ANT2") (pin "2") (pinfunction "2_2") (pintype "passive"))
      (node (ref "ANT2") (pin "3") (pinfunction "3_3") (pintype "passive"))
      (node (ref "ANT2") (pin "4") (pinfunction "4_4") (pintype "passive"))
      (node (ref "ANT2") (pin "5") (pinfunction "5_5") (pintype "passive"))
      (node (ref "C1") (pin "2") (pinfunction "2_2") (pintype "passive"))
      (node (ref "C10") (pin "2") (pinfunction "2_2") (pintype "passive"))
      (node (ref "C11") (pin "1") (pinfunction "1_1") (pintype "passive"))
      (node (ref "C12") (pin "2") (pinfunction "2_2") (pintype "passive"))
      (node (ref "C13") (pin "2") (pinfunction "2_2") (pintype "passive"))
      (node (ref "C14") (pin "2") (pinfunction "2_2") (pintype "passive"))
      (node (ref "C15") (pin "2") (pinfunction "2_2") (pintype "passive"))
      (node (ref "C16") (pin "2") (pinfunction "2_2") (pintype "passive"))
      (node (ref "C17") (pin "2") (pinfunction "2_2") (pintype "passive"))
      (node (ref "C18") (pin "2") (pinfunction "2_2") (pintype "passive"))
      (node (ref "C19") (pin "2") (pinfunction "2_2") (pintype "passive"))
      (node (ref "C2") (pin "1") (pinfunction "1_1") (pintype "passive"))
      (node (ref "C25") (pin "2") (pinfunction "2_2") (pintype "passive"))
      (node (ref "C26") (pin "1") (pinfunction "1_1") (pintype "passive"))
      (node (ref "C27") (pin "2") (pinfunction "2_2") (pintype "passive"))
      (node (ref "C28") (pin "2") (pinfunction "2_2") (pintype "passive"))
      (node (ref "C3") (pin "2") (pinfunction "2_2") (pintype "passive"))
      (node (ref "C34") (pin "1") (pinfunction "1_1") (pintype "passive"))
      (node (ref "C35") (pin "2") (pinfunction "2_2") (pintype "passive"))
      (node (ref "C36") (pin "2") (pinfunction "2_2") (pintype "passive"))
      (node (ref "C4") (pin "1") (pinfunction "1_1") (pintype "passive"))
      (node (ref "C5") (pin "1") (pinfunction "1_1") (pintype "passive"))
      (node (ref "C6") (pin "1") (pinfunction "1_1") (pintype "passive"))
      (node (ref "C7") (pin "2") (pinfunction "2_2") (pintype "passive"))
      (node (ref "C8") (pin "2") (pinfunction "2_2") (pintype "passive"))
      (node (ref "C9") (pin "2") (pinfunction "2_2") (pintype "passive"))
      (node (ref "CON1") (pin "4") (pinfunction "GND_4") (pintype "passive"))
      (node (ref "CON1") (pin "7") (pinfunction "GND_7") (pintype "passive"))
      (node (ref "CON1") (pin "8") (pinfunction "GND_8") (pintype "passive"))
      (node (ref "L4") (pin "1") (pinfunction "1_1") (pintype "passive"))
      (node (ref "P1") (pin "7") (pinfunction "7_7") (pintype "passive"))
      (node (ref "P2") (pin "6") (pinfunction "6_6") (pintype "passive"))
      (node (ref "P2") (pin "7") (pinfunction "7_7") (pintype "passive"))
      (node (ref "P5") (pin "1") (pinfunction "1_1") (pintype "passive"))
      (node (ref "P5") (pin "13") (pinfunction "13_13") (pintype "passive"))
      (node (ref "P5") (pin "19") (pinfunction "19_19") (pintype "passive"))
      (node (ref "P5") (pin "20") (pinfunction "20_20") (pintype "passive"))
      (node (ref "P5") (pin "25") (pinfunction "25_25") (pintype "passive"))
      (node (ref "P5") (pin "7") (pinfunction "7_7") (pintype "passive"))
      (node (ref "Q1") (pin "3") (pinfunction "S_3") (pintype "passive"))
      (node (ref "Q2") (pin "3") (pinfunction "S_3") (pintype "passive"))
      (node (ref "Q3") (pin "3") (pinfunction "S_3") (pintype "passive"))
      (node (ref "Q4") (pin "3") (pinfunction "S_3") (pintype "passive"))
      (node (ref "Q8") (pin "3") (pinfunction "S_3") (pintype "passive"))
      (node (ref "R13") (pin "1") (pinfunction "1_1") (pintype "passive"))
      (node (ref "R14") (pin "1") (pinfunction "1_1") (pintype "passive"))
      (node (ref "R15") (pin "1") (pinfunction "1_1") (pintype "passive"))
      (node (ref "R2") (pin "2") (pinfunction "2_2") (pintype "passive"))
      (node (ref "R27") (pin "1") (pinfunction "1_1") (pintype "passive"))
      (node (ref "R3") (pin "2") (pinfunction "2_2") (pintype "passive"))
      (node (ref "R44") (pin "1") (pinfunction "1_1") (pintype "passive"))
      (node (ref "R50") (pin "1") (pinfunction "1_1") (pintype "passive"))
      (node (ref "R6") (pin "1") (pinfunction "1_1") (pintype "passive"))
      (node (ref "R8") (pin "2") (pinfunction "2_2") (pintype "passive"))
      (node (ref "R9") (pin "2") (pinfunction "2_2") (pintype "passive"))
      (node (ref "SB9") (pin "2") (pinfunction "1_2") (pintype "passive"))
      (node (ref "U1") (pin "A13") (pinfunction "GND_A13") (pintype "power_in"))
      (node (ref "U1") (pin "A17") (pinfunction "GND_A17") (pintype "power_in"))
      (node (ref "U1") (pin "A3") (pinfunction "GND_A3") (pintype "power_in"))
      (node (ref "U1") (pin "A7") (pinfunction "GND_A7") (pintype "power_in"))
      (node (ref "U1") (pin "A9") (pinfunction "GND_A9") (pintype "power_in"))
      (node (ref "U1") (pin "B10") (pinfunction "GND_B10") (pintype "power_in"))
      (node (ref "U1") (pin "B12") (pinfunction "GND_B12") (pintype "power_in"))
      (node (ref "U1") (pin "B14") (pinfunction "GND_B14") (pintype "power_in"))
      (node (ref "U1") (pin "B16") (pinfunction "GND_B16") (pintype "power_in"))
      (node (ref "U1") (pin "B4") (pinfunction "GND_B4") (pintype "power_in"))
      (node (ref "U1") (pin "B6") (pinfunction "GND_B6") (pintype "power_in"))
      (node (ref "U1") (pin "C19") (pinfunction "GND_C19") (pintype "power_in"))
      (node (ref "U1") (pin "D18") (pinfunction "GND_D18") (pintype "power_in"))
      (node (ref "U1") (pin "F12") (pinfunction "GND_F12") (pintype "power_in"))
      (node (ref "U1") (pin "F18") (pinfunction "GND_F18") (pintype "power_in"))
      (node (ref "U1") (pin "F8") (pinfunction "GND_F8") (pintype "power_in"))
      (node (ref "U1") (pin "G19") (pinfunction "GND_G19") (pintype "power_in"))
      (node (ref "U1") (pin "H14") (pinfunction "GND_H14") (pintype "power_in"))
      (node (ref "U1") (pin "H6") (pinfunction "GND_H6") (pintype "power_in"))
      (node (ref "U1") (pin "J19") (pinfunction "GND_J19") (pintype "power_in"))
      (node (ref "U1") (pin "K18") (pinfunction "GND_K18") (pintype "power_in"))
      (node (ref "U1") (pin "M18") (pinfunction "GND_M18") (pintype "power_in"))
      (node (ref "U1") (pin "N19") (pinfunction "GND_N19") (pintype "power_in"))
      (node (ref "U1") (pin "P14") (pinfunction "GND_P14") (pintype "power_in"))
      (node (ref "U1") (pin "P6") (pinfunction "GND_P6") (pintype "power_in"))
      (node (ref "U1") (pin "T12") (pinfunction "GND_T12") (pintype "power_in"))
      (node (ref "U1") (pin "T8") (pinfunction "GND_T8") (pintype "power_in"))
      (node (ref "U1") (pin "U1") (pinfunction "GND_U1") (pintype "power_in"))
      (node (ref "U1") (pin "V2") (pinfunction "GND_V2") (pintype "power_in"))
      (node (ref "U1") (pin "W19") (pinfunction "GND_W19") (pintype "power_in"))
      (node (ref "U1") (pin "Y2") (pinfunction "GND_Y2") (pintype "power_in"))
      (node (ref "U1") (pin "Y4") (pinfunction "GND_Y4") (pintype "power_in"))
      (node (ref "U3") (pin "1") (pinfunction "GND_1") (pintype "passive"))
      (node (ref "U3") (pin "21") (pinfunction "GND_21") (pintype "passive"))
      (node (ref "U9") (pin "10") (pinfunction "PAD_10") (pintype "passive"))
      (node (ref "U9") (pin "3") (pinfunction "GND_3") (pintype "passive"))
      (node (ref "U9") (pin "5") (pinfunction "GND_5") (pintype "passive"))
      (node (ref "U9") (pin "9") (pinfunction "PAD_9") (pintype "passive"))
    )
    (net (code "71") (name "Net-(ANT1-Pad1)") (class "Default")
      (node (ref "ANT1") (pin "1") (pinfunction "1_1") (pintype "passive"))
      (node (ref "C15") (pin "1") (pinfunction "1_1") (pintype "passive"))
      (node (ref "L3") (pin "2") (pinfunction "2_2") (pintype "passive"))
    )
    (net (code "72") (name "Net-(ANT1-Pad2)") (class "Default")
      (node (ref "ANT1") (pin "2") (pinfunction "2_2") (pintype "passive"))
      (node (ref "L4") (pin "2") (pinfunction "2_2") (pintype "passive"))
    )
    (net (code "73") (name "Net-(ANT2-Pad1)") (class "Default")
      (node (ref "ANT2") (pin "1") (pinfunction "1_1") (pintype "passive"))
      (node (ref "R7") (pin "1") (pinfunction "1_1") (pintype "passive"))
      (node (ref "R9") (pin "1") (pinfunction "1_1") (pintype "passive"))
    )
    (net (code "74") (name "Net-(C17-Pad1)") (class "Default")
      (node (ref "C17") (pin "1") (pinfunction "1_1") (pintype "passive"))
      (node (ref "P4") (pin "6") (pinfunction "6_6") (pintype "passive"))
      (node (ref "R45") (pin "2") (pinfunction "2_2") (pintype "passive"))
    )
    (net (code "75") (name "Net-(C18-Pad1)") (class "Default")
      (node (ref "C18") (pin "1") (pinfunction "1_1") (pintype "passive"))
      (node (ref "R28") (pin "2") (pinfunction "2_2") (pintype "passive"))
      (node (ref "R45") (pin "1") (pinfunction "1_1") (pintype "passive"))
    )
    (net (code "76") (name "Net-(C19-Pad1)") (class "Default")
      (node (ref "C19") (pin "1") (pinfunction "1_1") (pintype "passive"))
      (node (ref "R28") (pin "1") (pinfunction "1_1") (pintype "passive"))
      (node (ref "R29") (pin "2") (pinfunction "2_2") (pintype "passive"))
    )
    (net (code "77") (name "Net-(D1-K)") (class "Default")
      (node (ref "D1") (pin "2") (pinfunction "K_2") (pintype "passive"))
      (node (ref "R12") (pin "1") (pinfunction "1_1") (pintype "passive"))
    )
    (net (code "78") (name "Net-(D7-K)") (class "Default")
      (node (ref "D7") (pin "2") (pinfunction "K_2") (pintype "passive"))
      (node (ref "R49") (pin "1") (pinfunction "1_1") (pintype "passive"))
    )
    (net (code "79") (name "Net-(L3-Pad1)") (class "Default")
      (node (ref "L3") (pin "1") (pinfunction "1_1") (pintype "passive"))
      (node (ref "R1") (pin "1") (pinfunction "1_1") (pintype "passive"))
      (node (ref "R3") (pin "1") (pinfunction "1_1") (pintype "passive"))
    )
    (net (code "80") (name "Net-(Q1-D)") (class "Default")
      (node (ref "Q1") (pin "2") (pinfunction "D_2") (pintype "passive"))
      (node (ref "SB3") (pin "2") (pinfunction "1_2") (pintype "passive"))
    )
    (net (code "81") (name "Net-(Q3-D)") (class "Default")
      (node (ref "Q3") (pin "2") (pinfunction "D_2") (pintype "passive"))
      (node (ref "R12") (pin "2") (pinfunction "2_2") (pintype "passive"))
    )
    (net (code "82") (name "Net-(Q4-D)") (class "Default")
      (node (ref "Q4") (pin "2") (pinfunction "D_2") (pintype "passive"))
      (node (ref "R5") (pin "1") (pinfunction "1_1") (pintype "passive"))
      (node (ref "SB6") (pin "2") (pinfunction "1_2") (pintype "passive"))
    )
    (net (code "83") (name "Net-(Q8-D)") (class "Default")
      (node (ref "Q8") (pin "2") (pinfunction "D_2") (pintype "passive"))
      (node (ref "R49") (pin "2") (pinfunction "2_2") (pintype "passive"))
    )
    (net (code "84") (name "Net-(Q8-G)") (class "Default")
      (node (ref "C28") (pin "1") (pinfunction "1_1") (pintype "passive"))
      (node (ref "Q8") (pin "1") (pinfunction "G_1") (pintype "passive"))
      (node (ref "R50") (pin "2") (pinfunction "2_2") (pintype "passive"))
      (node (ref "SB14") (pin "2") (pinfunction "1_2") (pintype "passive"))
    )
    (net (code "85") (name "Net-(R4-Pad2)") (class "Default")
      (node (ref "R4") (pin "2") (pinfunction "2_2") (pintype "passive"))
      (node (ref "S1") (pin "2") (pinfunction "2_2") (pintype "passive"))
      (node (ref "S1") (pin "3") (pinfunction "3_3") (pintype "passive"))
    )
    (net (code "86") (name "Net-(SB1-1)") (class "Default")
      (node (ref "P1") (pin "2") (pinfunction "2_2") (pintype "passive"))
      (node (ref "SB1") (pin "2") (pinfunction "1_2") (pintype "passive"))
    )
    (net (code "87") (name "Net-(SB2-1)") (class "Default")
      (node (ref "P1") (pin "1") (pinfunction "1_1") (pintype "passive"))
      (node (ref "SB2") (pin "2") (pinfunction "1_2") (pintype "passive"))
    )
    (net (code "88") (name "Net-(SB4-0)") (class "Default")
      (node (ref "S1") (pin "1") (pinfunction "1_1") (pintype "passive"))
      (node (ref "S1") (pin "4") (pinfunction "4_4") (pintype "passive"))
      (node (ref "SB4") (pin "1") (pinfunction "0_1") (pintype "passive"))
    )
    (net (code "89") (name "Net-(SB5-0)") (class "Default")
      (node (ref "C12") (pin "1") (pinfunction "1_1") (pintype "passive"))
      (node (ref "R4") (pin "1") (pinfunction "1_1") (pintype "passive"))
      (node (ref "SB5") (pin "1") (pinfunction "0_1") (pintype "passive"))
    )
    (net (code "90") (name "Net-(SB5-1)") (class "Default")
      (node (ref "SB5") (pin "2") (pinfunction "1_2") (pintype "passive"))
      (node (ref "U1") (pin "N4") (pinfunction "CTANK_N4") (pintype "passive"))
    )
    (net (code "91") (name "Net-(SB6-0)") (class "Default")
      (node (ref "SB6") (pin "1") (pinfunction "0_1") (pintype "passive"))
      (node (ref "U1") (pin "L16") (pinfunction "WAKE_RESERVED_L16") (pintype "passive"))
    )
    (net (code "92") (name "Net-(SB7-1)") (class "Default")
      (node (ref "SB7") (pin "2") (pinfunction "1_2") (pintype "passive"))
      (node (ref "U3") (pin "5") (pinfunction "A3_5") (pintype "passive"))
    )
    (net (code "93") (name "Net-(SB8-1)") (class "Default")
      (node (ref "SB8") (pin "2") (pinfunction "1_2") (pintype "passive"))
      (node (ref "U3") (pin "6") (pinfunction "A4_6") (pintype "passive"))
    )
    (net (code "94") (name "Net-(SB11-1)") (class "Default")
      (node (ref "R29") (pin "1") (pinfunction "1_1") (pintype "passive"))
      (node (ref "SB11") (pin "2") (pinfunction "1_2") (pintype "passive"))
    )
    (net (code "95") (name "Net-(U1-USB_VBUS)") (class "Default")
      (node (ref "R43") (pin "1") (pinfunction "1_1") (pintype "passive"))
      (node (ref "R44") (pin "2") (pinfunction "2_2") (pintype "passive"))
      (node (ref "U1") (pin "T18") (pinfunction "USB_VBUS_T18") (pintype "passive"))
    )
    (net (code "96") (name "Net-(U1-VBATT)") (class "Default")
      (node (ref "C4") (pin "2") (pinfunction "2_2") (pintype "passive"))
      (node (ref "C5") (pin "2") (pinfunction "2_2") (pintype "passive"))
      (node (ref "L1") (pin "1") (pinfunction "1_1") (pintype "passive"))
      (node (ref "U1") (pin "AA3") (pinfunction "VBATT_AA3") (pintype "power_in"))
      (node (ref "U1") (pin "W1") (pinfunction "VBATT_PA_W1") (pintype "passive"))
    )
    (net (code "97") (name "Net-(U3-EN)") (class "Default")
      (node (ref "C27") (pin "1") (pinfunction "1_1") (pintype "passive"))
      (node (ref "R46") (pin "1") (pinfunction "1_1") (pintype "passive"))
      (node (ref "U3") (pin "19") (pinfunction "VREFB_19") (pintype "passive"))
      (node (ref "U3") (pin "20") (pinfunction "EN_20") (pintype "passive"))
    )
    (net (code "98") (name "Net-(U9-LNAIN)") (class "Default")
      (node (ref "L2") (pin "1") (pinfunction "1_1") (pintype "passive"))
      (node (ref "U9") (pin "7") (pinfunction "LNAIN_7") (pintype "passive"))
    )
    (net (code "99") (name "Net-(U9-PreIN)") (class "Default")
      (node (ref "R7") (pin "2") (pinfunction "2_2") (pintype "passive"))
      (node (ref "R8") (pin "1") (pinfunction "1_1") (pintype "passive"))
      (node (ref "U9") (pin "4") (pinfunction "PreIN_4") (pintype "passive"))
    )
    (net (code "100") (name "Net-(U9-PreOUT)") (class "Default")
      (node (ref "L2") (pin "2") (pinfunction "2_2") (pintype "passive"))
      (node (ref "U9") (pin "6") (pinfunction "PreOUT_6") (pintype "passive"))
    )
    (net (code "101") (name "VSNK") (class "Default")
      (node (ref "P2") (pin "8") (pinfunction "8_8") (pintype "passive"))
      (node (ref "R43") (pin "2") (pinfunction "2_2") (pintype "passive"))
    )
    (net (code "102") (name "unconnected-(ANT1-Pad3)") (class "Default")
      (node (ref "ANT1") (pin "3") (pinfunction "3_3") (pintype "passive+no_connect"))
    )
    (net (code "103") (name "unconnected-(ANT1-Pad4)") (class "Default")
      (node (ref "ANT1") (pin "4") (pinfunction "4_4") (pintype "passive+no_connect"))
    )
    (net (code "104") (name "unconnected-(CON1-VPP-Pad5)") (class "Default")
      (node (ref "CON1") (pin "5") (pinfunction "VPP_5") (pintype "passive+no_connect"))
    )
    (net (code "105") (name "unconnected-(P1-Pad8)") (class "Default")
      (node (ref "P1") (pin "8") (pinfunction "8_8") (pintype "passive+no_connect"))
    )
    (net (code "106") (name "unconnected-(P2-Pad1)") (class "Default")
      (node (ref "P2") (pin "1") (pinfunction "1_1") (pintype "passive+no_connect"))
    )
    (net (code "107") (name "unconnected-(P2-Pad2)") (class "Default")
      (node (ref "P2") (pin "2") (pinfunction "2_2") (pintype "passive+no_connect"))
    )
    (net (code "108") (name "unconnected-(P2-Pad3)") (class "Default")
      (node (ref "P2") (pin "3") (pinfunction "3_3") (pintype "passive+no_connect"))
    )
    (net (code "109") (name "unconnected-(P4-Pad1)") (class "Default")
      (node (ref "P4") (pin "1") (pinfunction "1_1") (pintype "passive+no_connect"))
    )
    (net (code "110") (name "unconnected-(P4-Pad2)") (class "Default")
      (node (ref "P4") (pin "2") (pinfunction "2_2") (pintype "passive+no_connect"))
    )
    (net (code "111") (name "unconnected-(P4-Pad4)") (class "Default")
      (node (ref "P4") (pin "4") (pinfunction "4_4") (pintype "passive+no_connect"))
    )
    (net (code "112") (name "unconnected-(U1-RESERVED-PadA11)") (class "Default")
      (node (ref "U1") (pin "A11") (pinfunction "RESERVED_A11") (pintype "passive+no_connect"))
    )
    (net (code "113") (name "unconnected-(U1-RESERVED-PadA15)") (class "Default")
      (node (ref "U1") (pin "A15") (pinfunction "RESERVED_A15") (pintype "passive+no_connect"))
    )
    (net (code "114") (name "unconnected-(U1-RESERVED-PadB8)") (class "Default")
      (node (ref "U1") (pin "B8") (pinfunction "RESERVED_B8") (pintype "passive+no_connect"))
    )
    (net (code "115") (name "unconnected-(U1-RESERVED-PadG1)") (class "Default")
      (node (ref "U1") (pin "G1") (pinfunction "RESERVED_G1") (pintype "passive+no_connect"))
    )
    (net (code "116") (name "unconnected-(U1-RESERVED-PadG4)") (class "Default")
      (node (ref "U1") (pin "G4") (pinfunction "RESERVED_G4") (pintype "passive+no_connect"))
    )
    (net (code "117") (name "unconnected-(U1-RESERVED-PadH2)") (class "Default")
      (node (ref "U1") (pin "H2") (pinfunction "RESERVED_H2") (pintype "passive+no_connect"))
    )
    (net (code "118") (name "unconnected-(U1-RESERVED-PadJ1)") (class "Default")
      (node (ref "U1") (pin "J1") (pinfunction "RESERVED_J1") (pintype "passive+no_connect"))
    )
    (net (code "119") (name "unconnected-(U1-RESERVED-PadJ4)") (class "Default")
      (node (ref "U1") (pin "J4") (pinfunction "RESERVED_J4") (pintype "passive+no_connect"))
    )
    (net (code "120") (name "unconnected-(U1-RESERVED-PadJ16)") (class "Default")
      (node (ref "U1") (pin "J16") (pinfunction "RESERVED_J16") (pintype "passive+no_connect"))
    )
    (net (code "121") (name "unconnected-(U1-RESERVED-PadK2)") (class "Default")
      (node (ref "U1") (pin "K2") (pinfunction "RESERVED_K2") (pintype "passive+no_connect"))
    )
    (net (code "122") (name "unconnected-(U1-RESERVED-PadL19)") (class "Default")
      (node (ref "U1") (pin "L19") (pinfunction "RESERVED_L19") (pintype "passive+no_connect"))
    )
    (net (code "123") (name "unconnected-(U1-RESERVED-PadP18)") (class "Default")
      (node (ref "U1") (pin "P18") (pinfunction "RESERVED_P18") (pintype "passive+no_connect"))
    )
    (net (code "124") (name "unconnected-(U1-RESERVED-PadR4)") (class "Default")
      (node (ref "U1") (pin "R4") (pinfunction "RESERVED_R4") (pintype "passive+no_connect"))
    )
    (net (code "125") (name "unconnected-(U1-RESERVED-PadV7)") (class "Default")
      (node (ref "U1") (pin "V7") (pinfunction "RESERVED_V7") (pintype "passive+no_connect"))
    )
    (net (code "126") (name "unconnected-(U1-RESERVED-PadV9)") (class "Default")
      (node (ref "U1") (pin "V9") (pinfunction "RESERVED_V9") (pintype "passive+no_connect"))
    )
  )
)
